# SWD.net
KiCad netlist of a schematic drawn in Altium Designer
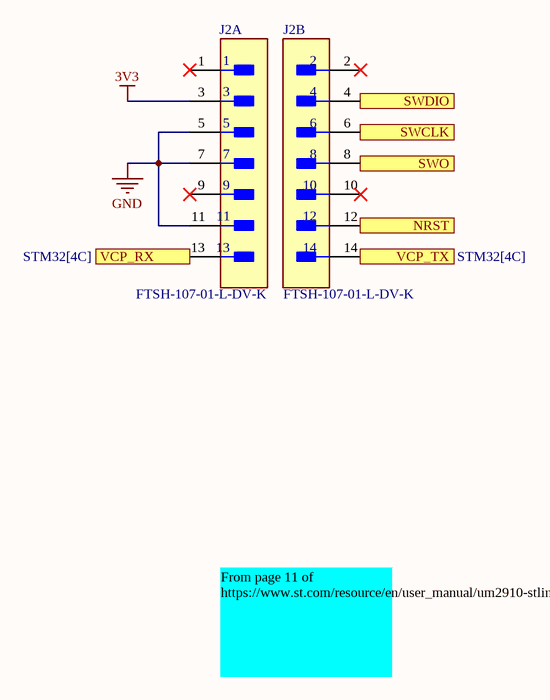
[diagram p0: SWD.SchDoc]

(export (version "E")
  (design (tool "Eeschema 10.0.6"))
  (components
    (comp (ref "J2")
      (value "FTSH-107-01-L-DV-K")
      (footprint "FP-FTSH-107-01-L-DV-K-MFG")
      (description "CONN HEADER SMD 14POS 1.27MM")
      (libsource (lib "") (part "7644e1a88aa4da17242a9b8d8257442_1"))
    )
  )
  (nets
    (net (code "1") (name "/NRST") (class "Default")
      (node (ref "J2") (pin "12") (pinfunction "12_12") (pintype "passive"))
    )
    (net (code "2") (name "/SWCLK") (class "Default")
      (node (ref "J2") (pin "6") (pinfunction "6_6") (pintype "passive"))
    )
    (net (code "3") (name "/SWDIO") (class "Default")
      (node (ref "J2") (pin "4") (pinfunction "4_4") (pintype "passive"))
    )
    (net (code "4") (name "/SWO") (class "Default")
      (node (ref "J2") (pin "8") (pinfunction "8_8") (pintype "passive"))
    )
    (net (code "5") (name "/VCP_RX") (class "Default")
      (node (ref "J2") (pin "13") (pinfunction "13_13") (pintype "passive"))
    )
    (net (code "6") (name "/VCP_TX") (class "Default")
      (node (ref "J2") (pin "14") (pinfunction "14_14") (pintype "passive"))
    )
    (net (code "7") (name "3V3") (class "Default")
      (node (ref "J2") (pin "3") (pinfunction "3_3") (pintype "passive"))
    )
    (net (code "8") (name "GND") (class "Default")
      (node (ref "J2") (pin "11") (pinfunction "11_11") (pintype "passive"))
      (node (ref "J2") (pin "5") (pinfunction "5_5") (pintype "passive"))
      (node (ref "J2") (pin "7") (pinfunction "7_7") (pintype "passive"))
    )
    (net (code "9") (name "unconnected-(J2-Pad1)") (class "Default")
      (node (ref "J2") (pin "1") (pinfunction "1_1") (pintype "passive+no_connect"))
    )
    (net (code "10") (name "unconnected-(J2-Pad2)") (class "Default")
      (node (ref "J2") (pin "2") (pinfunction "2_2") (pintype "passive+no_connect"))
    )
    (net (code "11") (name "unconnected-(J2-Pad9)") (class "Default")
      (node (ref "J2") (pin "9") (pinfunction "9_9") (pintype "passive+no_connect"))
    )
    (net (code "12") (name "unconnected-(J2-Pad10)") (class "Default")
      (node (ref "J2") (pin "10") (pinfunction "10_10") (pintype "passive+no_connect"))
    )
  )
)
